# FPGA.net
KiCad netlist of a schematic drawn in Altium Designer
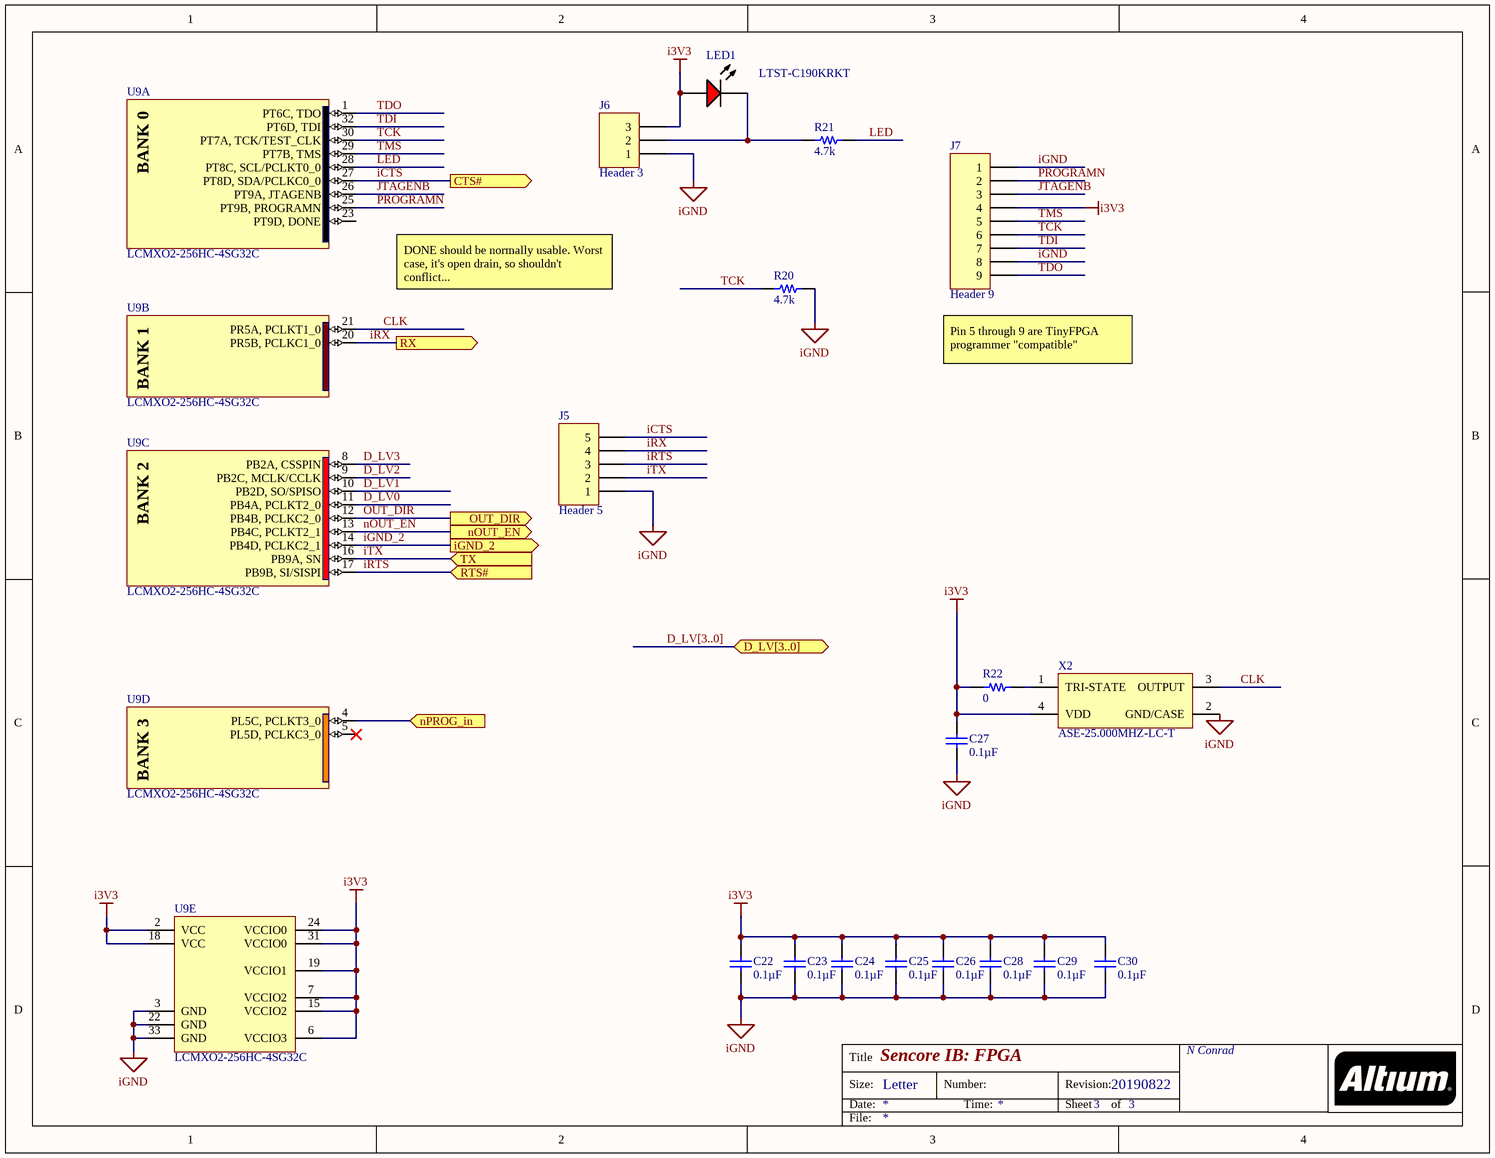
[diagram p0: FPGA.SchDoc]

(export (version "E")
  (design (tool "Eeschema 10.0.6"))
  (components
    (comp (ref "C22")
      (value "0.1µF")
      (footprint "CAPC1608X09L_GRM")
      (description "CAP CER 0.1UF 50V X7R 0603")
      (fields (field (name "PART NUMBER") "GCJ188R71H104KA12D") (field (name "TOLERANCE") "±10%"))
      (libsource (lib "ComponentDB") (part "Capacitor"))
    )
    (comp (ref "C23")
      (value "0.1µF")
      (footprint "CAPC1608X09L_GRM")
      (description "CAP CER 0.1UF 50V X7R 0603")
      (fields (field (name "PART NUMBER") "GCJ188R71H104KA12D") (field (name "TOLERANCE") "±10%"))
      (libsource (lib "ComponentDB") (part "Capacitor"))
    )
    (comp (ref "C24")
      (value "0.1µF")
      (footprint "CAPC1608X09L_GRM")
      (description "CAP CER 0.1UF 50V X7R 0603")
      (fields (field (name "PART NUMBER") "GCJ188R71H104KA12D") (field (name "TOLERANCE") "±10%"))
      (libsource (lib "ComponentDB") (part "Capacitor"))
    )
    (comp (ref "C25")
      (value "0.1µF")
      (footprint "CAPC1608X09L_GRM")
      (description "CAP CER 0.1UF 50V X7R 0603")
      (fields (field (name "PART NUMBER") "GCJ188R71H104KA12D") (field (name "TOLERANCE") "±10%"))
      (libsource (lib "ComponentDB") (part "Capacitor"))
    )
    (comp (ref "C26")
      (value "0.1µF")
      (footprint "CAPC1608X09L_GRM")
      (description "CAP CER 0.1UF 50V X7R 0603")
      (fields (field (name "PART NUMBER") "GCJ188R71H104KA12D") (field (name "TOLERANCE") "±10%"))
      (libsource (lib "ComponentDB") (part "Capacitor"))
    )
    (comp (ref "C27")
      (value "0.1µF")
      (footprint "CAPC1608X09L_GRM")
      (description "CAP CER 0.1UF 50V X7R 0603")
      (fields (field (name "PART NUMBER") "GCJ188R71H104KA12D") (field (name "TOLERANCE") "±10%"))
      (libsource (lib "ComponentDB") (part "Capacitor"))
    )
    (comp (ref "C28")
      (value "0.1µF")
      (footprint "CAPC1608X09L_GRM")
      (description "CAP CER 0.1UF 50V X7R 0603")
      (fields (field (name "PART NUMBER") "GCJ188R71H104KA12D") (field (name "TOLERANCE") "±10%"))
      (libsource (lib "ComponentDB") (part "Capacitor"))
    )
    (comp (ref "C29")
      (value "0.1µF")
      (footprint "CAPC1608X09L_GRM")
      (description "CAP CER 0.1UF 50V X7R 0603")
      (fields (field (name "PART NUMBER") "GCJ188R71H104KA12D") (field (name "TOLERANCE") "±10%"))
      (libsource (lib "ComponentDB") (part "Capacitor"))
    )
    (comp (ref "C30")
      (value "0.1µF")
      (footprint "CAPC1608X09L_GRM")
      (description "CAP CER 0.1UF 50V X7R 0603")
      (fields (field (name "PART NUMBER") "GCJ188R71H104KA12D") (field (name "TOLERANCE") "±10%"))
      (libsource (lib "ComponentDB") (part "Capacitor"))
    )
    (comp (ref "J5")
      (value "Header 5")
      (footprint "HDR1X5")
      (description "Header, 5-Pin")
      (fields (field (name "PUBLISHER") "Altium Limited"))
      (libsource (lib "Miscellaneous Connectors") (part "Header 5"))
    )
    (comp (ref "J6")
      (value "Header 3")
      (footprint "HDR1X3")
      (description "Header, 3-Pin")
      (fields (field (name "PUBLISHER") "Altium Limited"))
      (libsource (lib "Miscellaneous Connectors") (part "Header 3"))
    )
    (comp (ref "J7")
      (value "Header 9")
      (footprint "HDR1X9")
      (description "Header, 9-Pin")
      (fields (field (name "PUBLISHER") "Altium Limited"))
      (libsource (lib "Miscellaneous Connectors") (part "Header 9"))
    )
    (comp (ref "LED1")
      (value "LTST-C190KRKT")
      (footprint "LTST-C191KRKT_V")
      (description "LED Uni-Color Red, 62.5 mW, 5 V, -30 to 85 degC, 2-Pin SMD, RoHS, Tape and Reel")
      (fields (field (name "TOLERANCE") "20%"))
      (libsource (lib "Altium Content Vault") (part "LED-RED-AK-2"))
    )
    (comp (ref "R20")
      (value "4.7k")
      (footprint "RESC1608X06L_Yageo0603")
      (description "RES SMD 4.7K OHM 5% 1/10W 0603")
      (fields (field (name "PART NUMBER") "RC0603JR-074K7L") (field (name "TOLERANCE") "±5%"))
      (libsource (lib "ComponentDB") (part "Resistor"))
    )
    (comp (ref "R21")
      (value "4.7k")
      (footprint "RESC1608X06L_Yageo0603")
      (description "RES SMD 4.7K OHM 5% 1/10W 0603")
      (fields (field (name "PART NUMBER") "RC0603JR-074K7L") (field (name "TOLERANCE") "±5%"))
      (libsource (lib "ComponentDB") (part "Resistor"))
    )
    (comp (ref "R22")
      (value "0")
      (footprint "RESC1608X06L_Yageo0603")
      (description "RES SMD 0 OHM JUMPER 1/10W 0603")
      (fields (field (name "PART NUMBER") "RC0603JR-070RL") (field (name "TOLERANCE") "Jumper"))
      (libsource (lib "ComponentDB") (part "Resistor"))
    )
    (comp (ref "U9")
      (value "LCMXO2-256HC-4SG32C")
      (footprint "QFN50P500X500X60_HS-33NH_Lattice_QFN32_SG32C")
      (description "IC FPGA 21 I/O 32QFN")
      (fields (field (name "MANUFACTURER PART NUMBER 1") "LCMXO2-256HC-4SG32C"))
      (libsource (lib "PartLibNJC") (part "LCMXO2-256HC-4SG32C"))
    )
    (comp (ref "X2")
      (value "ASE-25.000MHZ-LC-T")
      (footprint "ABRA-ASE_V")
      (fields (field (name "MANUFACTURER") "Abracon"))
      (libsource (lib "Altium Content Vault") (part "ABRA-ASE2-4"))
    )
  )
  (nets
    (net (code "1") (name "/CLK") (class "Default")
      (node (ref "U9") (pin "21") (pinfunction "PR5A,_PCLKT1_0_21") (pintype "bidirectional"))
      (node (ref "X2") (pin "3") (pinfunction "OUTPUT_3") (pintype "passive"))
    )
    (net (code "2") (name "/D_LV0") (class "Default")
      (node (ref "U9") (pin "11") (pinfunction "PB4A,_PCLKT2_0_11") (pintype "bidirectional"))
    )
    (net (code "3") (name "/D_LV1") (class "Default")
      (node (ref "U9") (pin "10") (pinfunction "PB2D,_SO/SPISO_10") (pintype "bidirectional"))
    )
    (net (code "4") (name "/D_LV2") (class "Default")
      (node (ref "U9") (pin "9") (pinfunction "PB2C,_MCLK/CCLK_9") (pintype "bidirectional"))
    )
    (net (code "5") (name "/D_LV3") (class "Default")
      (node (ref "U9") (pin "8") (pinfunction "PB2A,_CSSPIN_8") (pintype "bidirectional"))
    )
    (net (code "7") (name "/JTAGENB") (class "Default")
      (node (ref "J7") (pin "3") (pinfunction "3_3") (pintype "passive"))
      (node (ref "U9") (pin "26") (pinfunction "PT9A,_JTAGENB_26") (pintype "bidirectional"))
    )
    (net (code "8") (name "/LED") (class "Default")
      (node (ref "R21") (pin "2") (pinfunction "2_2") (pintype "passive"))
      (node (ref "U9") (pin "28") (pinfunction "PT8C,_SCL/PCLKT0_0_28") (pintype "bidirectional"))
    )
    (net (code "9") (name "/OUT_DIR") (class "Default")
      (node (ref "U9") (pin "12") (pinfunction "PB4B,_PCLKC2_0_12") (pintype "bidirectional"))
    )
    (net (code "10") (name "/PROGRAMN") (class "Default")
      (node (ref "J7") (pin "2") (pinfunction "2_2") (pintype "passive"))
      (node (ref "U9") (pin "25") (pinfunction "PT9B,_PROGRAMN_25") (pintype "bidirectional"))
    )
    (net (code "11") (name "/TCK") (class "Default")
      (node (ref "J7") (pin "6") (pinfunction "6_6") (pintype "passive"))
      (node (ref "R20") (pin "1") (pinfunction "1_1") (pintype "passive"))
      (node (ref "U9") (pin "30") (pinfunction "PT7A,_TCK/TEST_CLK_30") (pintype "bidirectional"))
    )
    (net (code "12") (name "/TDI") (class "Default")
      (node (ref "J7") (pin "7") (pinfunction "7_7") (pintype "passive"))
      (node (ref "U9") (pin "32") (pinfunction "PT6D,_TDI_32") (pintype "bidirectional"))
    )
    (net (code "13") (name "/TDO") (class "Default")
      (node (ref "J7") (pin "9") (pinfunction "9_9") (pintype "passive"))
      (node (ref "U9") (pin "1") (pinfunction "PT6C,_TDO_1") (pintype "bidirectional"))
    )
    (net (code "14") (name "/TMS") (class "Default")
      (node (ref "J7") (pin "5") (pinfunction "5_5") (pintype "passive"))
      (node (ref "U9") (pin "29") (pinfunction "PT7B,_TMS_29") (pintype "bidirectional"))
    )
    (net (code "15") (name "/iCTS") (class "Default")
      (node (ref "J5") (pin "5") (pinfunction "5_5") (pintype "passive"))
      (node (ref "U9") (pin "27") (pinfunction "PT8D,_SDA/PCLKC0_0_27") (pintype "bidirectional"))
    )
    (net (code "16") (name "/iGND_2") (class "Default")
      (node (ref "U9") (pin "14") (pinfunction "PB4D,_PCLKC2_1_14") (pintype "bidirectional"))
    )
    (net (code "17") (name "/iRTS") (class "Default")
      (node (ref "J5") (pin "3") (pinfunction "3_3") (pintype "passive"))
      (node (ref "U9") (pin "17") (pinfunction "PB9B,_SI/SISPI_17") (pintype "bidirectional"))
    )
    (net (code "18") (name "/iRX") (class "Default")
      (node (ref "J5") (pin "4") (pinfunction "4_4") (pintype "passive"))
      (node (ref "U9") (pin "20") (pinfunction "PR5B,_PCLKC1_0_20") (pintype "bidirectional"))
    )
    (net (code "19") (name "/iTX") (class "Default")
      (node (ref "J5") (pin "2") (pinfunction "2_2") (pintype "passive"))
      (node (ref "U9") (pin "16") (pinfunction "PB9A,_SN_16") (pintype "bidirectional"))
    )
    (net (code "20") (name "/nOUT_EN") (class "Default")
      (node (ref "U9") (pin "13") (pinfunction "PB4C,_PCLKT2_1_13") (pintype "bidirectional"))
    )
    (net (code "21") (name "/nPROG_in") (class "Default")
      (node (ref "U9") (pin "4") (pinfunction "PL5C,_PCLKT3_0_4") (pintype "bidirectional"))
    )
    (net (code "22") (name "Net-(LED1-K)") (class "Default")
      (node (ref "J6") (pin "2") (pinfunction "2_2") (pintype "passive"))
      (node (ref "LED1") (pin "2") (pinfunction "K_2") (pintype "passive"))
      (node (ref "R21") (pin "1") (pinfunction "1_1") (pintype "passive"))
    )
    (net (code "23") (name "Net-(X2-TRI-STATE)") (class "Default")
      (node (ref "R22") (pin "1") (pinfunction "1_1") (pintype "passive"))
      (node (ref "X2") (pin "1") (pinfunction "TRI-STATE_1") (pintype "passive"))
    )
    (net (code "24") (name "i3V3") (class "Default")
      (node (ref "C22") (pin "2") (pinfunction "2_2") (pintype "passive"))
      (node (ref "C23") (pin "2") (pinfunction "2_2") (pintype "passive"))
      (node (ref "C24") (pin "2") (pinfunction "2_2") (pintype "passive"))
      (node (ref "C25") (pin "2") (pinfunction "2_2") (pintype "passive"))
      (node (ref "C26") (pin "2") (pinfunction "2_2") (pintype "passive"))
      (node (ref "C27") (pin "2") (pinfunction "2_2") (pintype "passive"))
      (node (ref "C28") (pin "2") (pinfunction "2_2") (pintype "passive"))
      (node (ref "C29") (pin "2") (pinfunction "2_2") (pintype "passive"))
      (node (ref "C30") (pin "2") (pinfunction "2_2") (pintype "passive"))
      (node (ref "J6") (pin "3") (pinfunction "3_3") (pintype "passive"))
      (node (ref "J7") (pin "4") (pinfunction "4_4") (pintype "passive"))
      (node (ref "LED1") (pin "1") (pinfunction "A_1") (pintype "passive"))
      (node (ref "R22") (pin "2") (pinfunction "2_2") (pintype "passive"))
      (node (ref "U9") (pin "15") (pinfunction "VCCIO2_15") (pintype "power_in"))
      (node (ref "U9") (pin "18") (pinfunction "VCC_18") (pintype "power_in"))
      (node (ref "U9") (pin "19") (pinfunction "VCCIO1_19") (pintype "power_in"))
      (node (ref "U9") (pin "2") (pinfunction "VCC_2") (pintype "power_in"))
      (node (ref "U9") (pin "24") (pinfunction "VCCIO0_24") (pintype "power_in"))
      (node (ref "U9") (pin "31") (pinfunction "VCCIO0_31") (pintype "power_in"))
      (node (ref "U9") (pin "6") (pinfunction "VCCIO3_6") (pintype "power_in"))
      (node (ref "U9") (pin "7") (pinfunction "VCCIO2_7") (pintype "power_in"))
      (node (ref "X2") (pin "4") (pinfunction "VDD_4") (pintype "power_in"))
    )
    (net (code "25") (name "iGND") (class "Default")
      (node (ref "C22") (pin "1") (pinfunction "1_1") (pintype "passive"))
      (node (ref "C23") (pin "1") (pinfunction "1_1") (pintype "passive"))
      (node (ref "C24") (pin "1") (pinfunction "1_1") (pintype "passive"))
      (node (ref "C25") (pin "1") (pinfunction "1_1") (pintype "passive"))
      (node (ref "C26") (pin "1") (pinfunction "1_1") (pintype "passive"))
      (node (ref "C27") (pin "1") (pinfunction "1_1") (pintype "passive"))
      (node (ref "C28") (pin "1") (pinfunction "1_1") (pintype "passive"))
      (node (ref "C29") (pin "1") (pinfunction "1_1") (pintype "passive"))
      (node (ref "C30") (pin "1") (pinfunction "1_1") (pintype "passive"))
      (node (ref "J5") (pin "1") (pinfunction "1_1") (pintype "passive"))
      (node (ref "J6") (pin "1") (pinfunction "1_1") (pintype "passive"))
      (node (ref "J7") (pin "1") (pinfunction "1_1") (pintype "passive"))
      (node (ref "J7") (pin "8") (pinfunction "8_8") (pintype "passive"))
      (node (ref "R20") (pin "2") (pinfunction "2_2") (pintype "passive"))
      (node (ref "U9") (pin "22") (pinfunction "GND_22") (pintype "power_in"))
      (node (ref "U9") (pin "3") (pinfunction "GND_3") (pintype "power_in"))
      (node (ref "U9") (pin "33") (pinfunction "GND_33") (pintype "power_in"))
      (node (ref "X2") (pin "2") (pinfunction "GND/CASE_2") (pintype "power_in"))
    )
    (net (code "26") (name "unconnected-(U9A-PT9D,_DONE-Pad23)") (class "Default")
      (node (ref "U9") (pin "23") (pinfunction "PT9D,_DONE_23") (pintype "bidirectional"))
    )
    (net (code "27") (name "unconnected-(U9D-PL5D,_PCLKC3_0-Pad5)") (class "Default")
      (node (ref "U9") (pin "5") (pinfunction "PL5D,_PCLKC3_0_5") (pintype "bidirectional+no_connect"))
    )
  )
)
